# zumo_cam_01.net
KiCad netlist of a schematic drawn in EAGLE
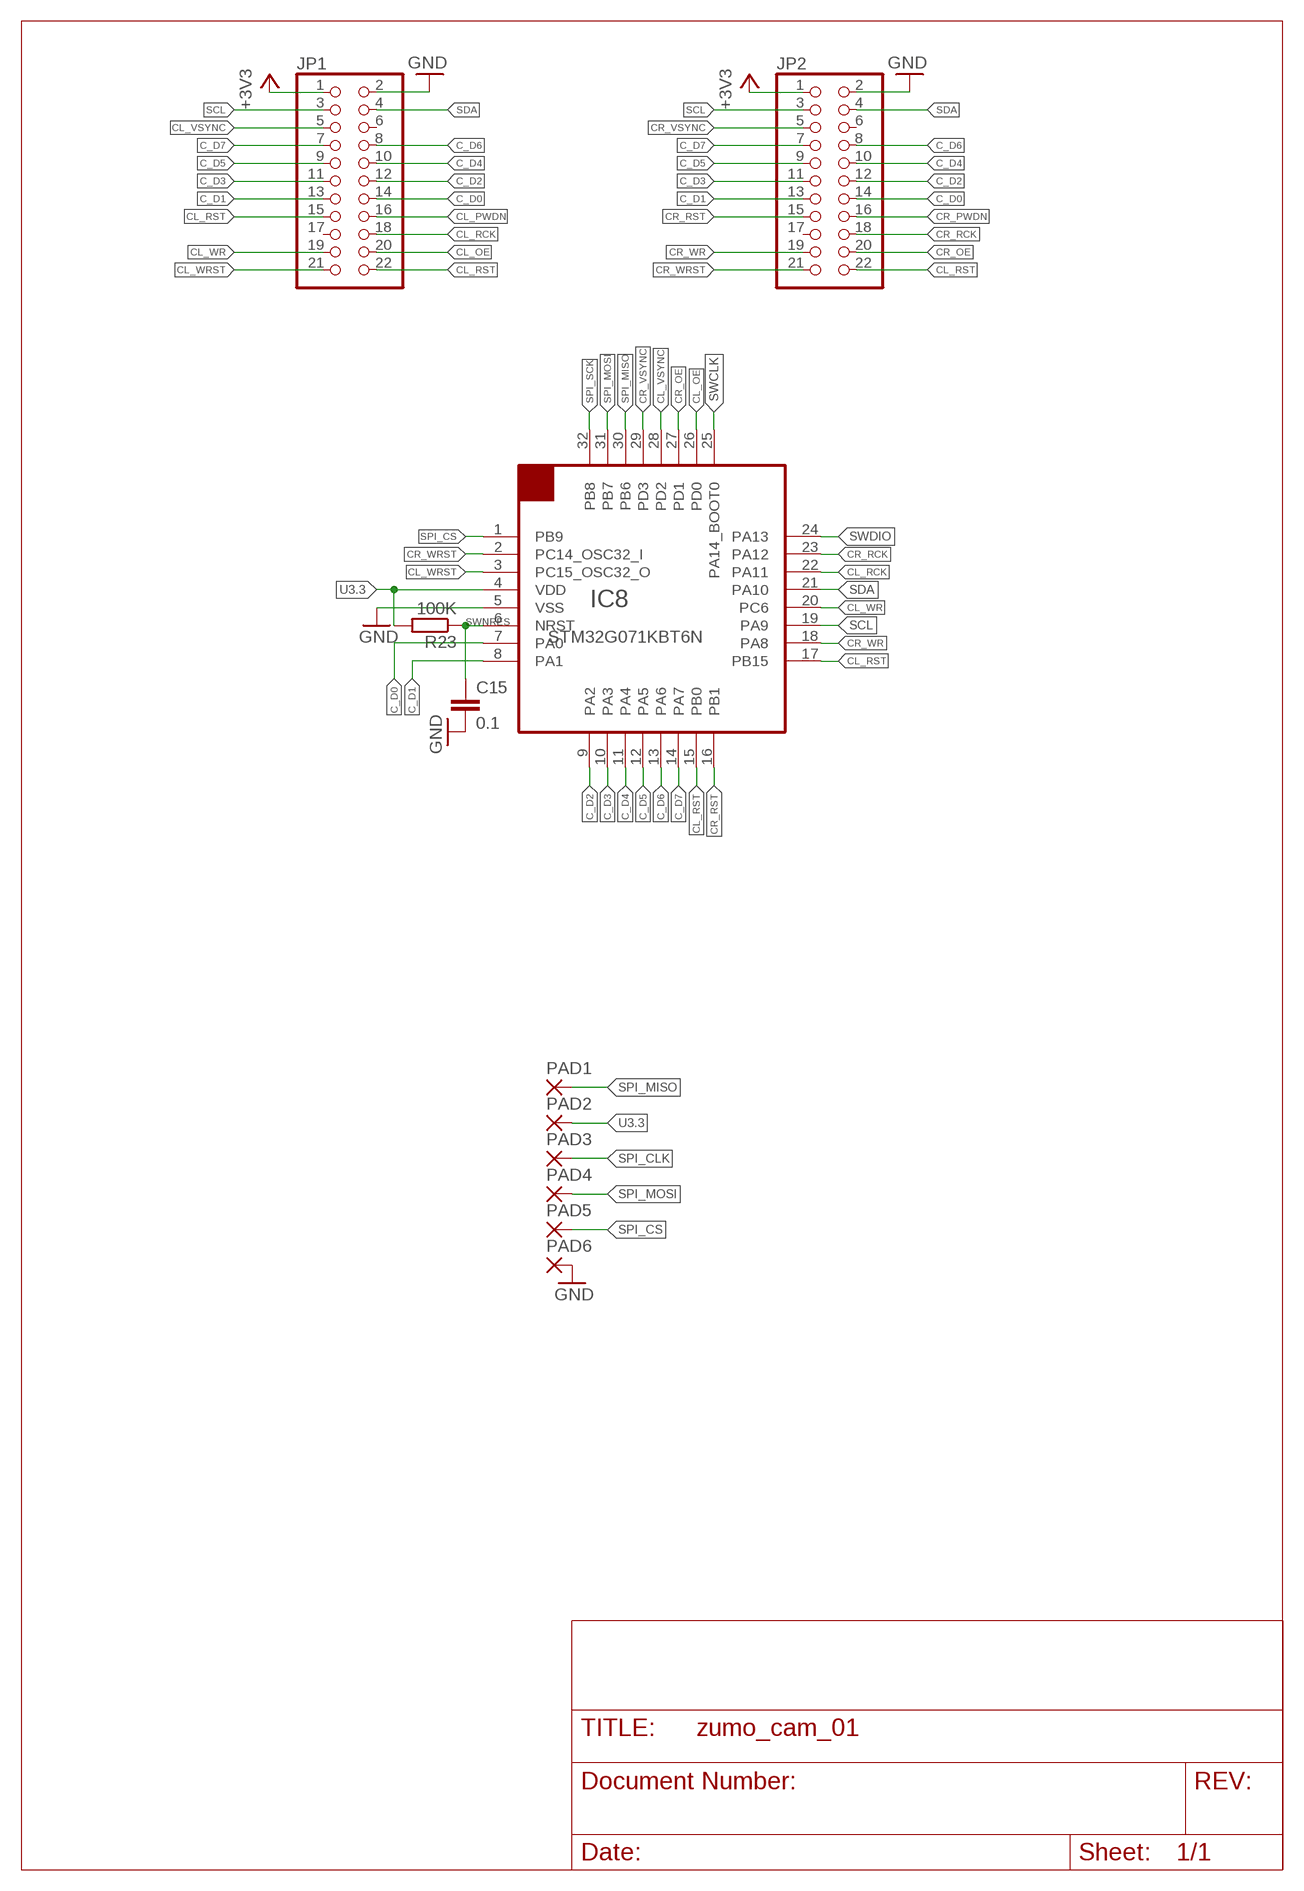
[diagram p0: schematic, sheet 1]

(export (version "E")
  (design (tool "Eeschema 10.0.6"))
  (components
    (comp (ref "C15")
      (value "0.1")
      (footprint "eagle-import:C0805")
      (libsource (lib "eagle-import") (part "C-EUC0805"))
    )
    (comp (ref "IC8")
      (value "STM32G071KBT6N")
      (footprint "eagle-import:LQFP-32")
      (libsource (lib "eagle-import") (part "STM32G071KBT6N"))
    )
    (comp (ref "JP1")
      (value "PINHD-2X11_2.54-SMD")
      (footprint "eagle-import:2X11SMD")
      (libsource (lib "eagle-import") (part "PINHD-2X11_2.54-SMD"))
    )
    (comp (ref "JP2")
      (value "PINHD-2X11_2.54-SMD")
      (footprint "eagle-import:2X11SMD")
      (libsource (lib "eagle-import") (part "PINHD-2X11_2.54-SMD"))
    )
    (comp (ref "PAD1")
      (value "SMD2")
      (footprint "eagle-import:SMD1,27-2,54")
      (libsource (lib "eagle-import") (part "SMD2"))
    )
    (comp (ref "PAD2")
      (value "SMD2")
      (footprint "eagle-import:SMD1,27-2,54")
      (libsource (lib "eagle-import") (part "SMD2"))
    )
    (comp (ref "PAD3")
      (value "SMD2")
      (footprint "eagle-import:SMD1,27-2,54")
      (libsource (lib "eagle-import") (part "SMD2"))
    )
    (comp (ref "PAD4")
      (value "SMD2")
      (footprint "eagle-import:SMD1,27-2,54")
      (libsource (lib "eagle-import") (part "SMD2"))
    )
    (comp (ref "PAD5")
      (value "SMD2")
      (footprint "eagle-import:SMD1,27-2,54")
      (libsource (lib "eagle-import") (part "SMD2"))
    )
    (comp (ref "PAD6")
      (value "SMD2")
      (footprint "eagle-import:SMD1,27-2,54")
      (libsource (lib "eagle-import") (part "SMD2"))
    )
    (comp (ref "R23")
      (value "100K")
      (footprint "eagle-import:R0805")
      (libsource (lib "eagle-import") (part "R-EU_R0805"))
    )
  )
  (nets
    (net (code "1") (name "+3V3") (class "Default")
      (node (ref "JP1") (pin "1") (pinfunction "1_1") (pintype "passive"))
      (node (ref "JP2") (pin "1") (pinfunction "1_1") (pintype "passive"))
    )
    (net (code "2") (name "/SWNRES") (class "Default")
      (node (ref "C15") (pin "1") (pinfunction "1_1") (pintype "passive"))
      (node (ref "IC8") (pin "6") (pinfunction "NRST_6") (pintype "bidirectional"))
      (node (ref "R23") (pin "1") (pinfunction "1_1") (pintype "passive"))
    )
    (net (code "3") (name "CL_OE") (class "Default")
      (node (ref "IC8") (pin "26") (pinfunction "PD0_26") (pintype "bidirectional"))
      (node (ref "JP1") (pin "20") (pinfunction "20_20") (pintype "passive"))
    )
    (net (code "4") (name "CL_PWDN") (class "Default")
      (node (ref "JP1") (pin "16") (pinfunction "16_16") (pintype "passive"))
    )
    (net (code "5") (name "CL_RCK") (class "Default")
      (node (ref "IC8") (pin "22") (pinfunction "PA11_22") (pintype "bidirectional"))
      (node (ref "JP1") (pin "18") (pinfunction "18_18") (pintype "passive"))
    )
    (net (code "6") (name "CL_RST") (class "Default")
      (node (ref "IC8") (pin "15") (pinfunction "PB0_15") (pintype "bidirectional"))
      (node (ref "IC8") (pin "17") (pinfunction "PB15_17") (pintype "bidirectional"))
      (node (ref "JP1") (pin "15") (pinfunction "15_15") (pintype "passive"))
      (node (ref "JP1") (pin "22") (pinfunction "22_22") (pintype "passive"))
      (node (ref "JP2") (pin "22") (pinfunction "22_22") (pintype "passive"))
    )
    (net (code "7") (name "CL_VSYNC") (class "Default")
      (node (ref "IC8") (pin "28") (pinfunction "PD2_28") (pintype "bidirectional"))
      (node (ref "JP1") (pin "5") (pinfunction "5_5") (pintype "passive"))
    )
    (net (code "8") (name "CL_WR") (class "Default")
      (node (ref "IC8") (pin "20") (pinfunction "PC6_20") (pintype "bidirectional"))
      (node (ref "JP1") (pin "19") (pinfunction "19_19") (pintype "passive"))
    )
    (net (code "9") (name "CL_WRST") (class "Default")
      (node (ref "IC8") (pin "3") (pinfunction "PC15_OSC32_O_3") (pintype "bidirectional"))
      (node (ref "JP1") (pin "21") (pinfunction "21_21") (pintype "passive"))
    )
    (net (code "10") (name "CR_OE") (class "Default")
      (node (ref "IC8") (pin "27") (pinfunction "PD1_27") (pintype "bidirectional"))
      (node (ref "JP2") (pin "20") (pinfunction "20_20") (pintype "passive"))
    )
    (net (code "11") (name "CR_PWDN") (class "Default")
      (node (ref "JP2") (pin "16") (pinfunction "16_16") (pintype "passive"))
    )
    (net (code "12") (name "CR_RCK") (class "Default")
      (node (ref "IC8") (pin "23") (pinfunction "PA12_23") (pintype "bidirectional"))
      (node (ref "JP2") (pin "18") (pinfunction "18_18") (pintype "passive"))
    )
    (net (code "13") (name "CR_RST") (class "Default")
      (node (ref "IC8") (pin "16") (pinfunction "PB1_16") (pintype "bidirectional"))
      (node (ref "JP2") (pin "15") (pinfunction "15_15") (pintype "passive"))
    )
    (net (code "14") (name "CR_VSYNC") (class "Default")
      (node (ref "IC8") (pin "29") (pinfunction "PD3_29") (pintype "bidirectional"))
      (node (ref "JP2") (pin "5") (pinfunction "5_5") (pintype "passive"))
    )
    (net (code "15") (name "CR_WR") (class "Default")
      (node (ref "IC8") (pin "18") (pinfunction "PA8_18") (pintype "bidirectional"))
      (node (ref "JP2") (pin "19") (pinfunction "19_19") (pintype "passive"))
    )
    (net (code "16") (name "CR_WRST") (class "Default")
      (node (ref "IC8") (pin "2") (pinfunction "PC14_OSC32_I_2") (pintype "bidirectional"))
      (node (ref "JP2") (pin "21") (pinfunction "21_21") (pintype "passive"))
    )
    (net (code "17") (name "C_D0") (class "Default")
      (node (ref "IC8") (pin "7") (pinfunction "PA0_7") (pintype "bidirectional"))
      (node (ref "JP1") (pin "14") (pinfunction "14_14") (pintype "passive"))
      (node (ref "JP2") (pin "14") (pinfunction "14_14") (pintype "passive"))
    )
    (net (code "18") (name "C_D1") (class "Default")
      (node (ref "IC8") (pin "8") (pinfunction "PA1_8") (pintype "bidirectional"))
      (node (ref "JP1") (pin "13") (pinfunction "13_13") (pintype "passive"))
      (node (ref "JP2") (pin "13") (pinfunction "13_13") (pintype "passive"))
    )
    (net (code "19") (name "C_D2") (class "Default")
      (node (ref "IC8") (pin "9") (pinfunction "PA2_9") (pintype "bidirectional"))
      (node (ref "JP1") (pin "12") (pinfunction "12_12") (pintype "passive"))
      (node (ref "JP2") (pin "12") (pinfunction "12_12") (pintype "passive"))
    )
    (net (code "20") (name "C_D3") (class "Default")
      (node (ref "IC8") (pin "10") (pinfunction "PA3_10") (pintype "bidirectional"))
      (node (ref "JP1") (pin "11") (pinfunction "11_11") (pintype "passive"))
      (node (ref "JP2") (pin "11") (pinfunction "11_11") (pintype "passive"))
    )
    (net (code "21") (name "C_D4") (class "Default")
      (node (ref "IC8") (pin "11") (pinfunction "PA4_11") (pintype "bidirectional"))
      (node (ref "JP1") (pin "10") (pinfunction "10_10") (pintype "passive"))
      (node (ref "JP2") (pin "10") (pinfunction "10_10") (pintype "passive"))
    )
    (net (code "22") (name "C_D5") (class "Default")
      (node (ref "IC8") (pin "12") (pinfunction "PA5_12") (pintype "bidirectional"))
      (node (ref "JP1") (pin "9") (pinfunction "9_9") (pintype "passive"))
      (node (ref "JP2") (pin "9") (pinfunction "9_9") (pintype "passive"))
    )
    (net (code "23") (name "C_D6") (class "Default")
      (node (ref "IC8") (pin "13") (pinfunction "PA6_13") (pintype "bidirectional"))
      (node (ref "JP1") (pin "8") (pinfunction "8_8") (pintype "passive"))
      (node (ref "JP2") (pin "8") (pinfunction "8_8") (pintype "passive"))
    )
    (net (code "24") (name "C_D7") (class "Default")
      (node (ref "IC8") (pin "14") (pinfunction "PA7_14") (pintype "bidirectional"))
      (node (ref "JP1") (pin "7") (pinfunction "7_7") (pintype "passive"))
      (node (ref "JP2") (pin "7") (pinfunction "7_7") (pintype "passive"))
    )
    (net (code "25") (name "GND") (class "Default")
      (node (ref "C15") (pin "2") (pinfunction "2_2") (pintype "passive"))
      (node (ref "IC8") (pin "5") (pinfunction "VSS_5") (pintype "power_in"))
      (node (ref "JP1") (pin "2") (pinfunction "2_2") (pintype "passive"))
      (node (ref "JP2") (pin "2") (pinfunction "2_2") (pintype "passive"))
      (node (ref "PAD6") (pin "1") (pinfunction "P_1") (pintype "passive"))
    )
    (net (code "26") (name "SCL") (class "Default")
      (node (ref "IC8") (pin "19") (pinfunction "PA9_19") (pintype "bidirectional"))
      (node (ref "JP1") (pin "3") (pinfunction "3_3") (pintype "passive"))
      (node (ref "JP2") (pin "3") (pinfunction "3_3") (pintype "passive"))
    )
    (net (code "27") (name "SDA") (class "Default")
      (node (ref "IC8") (pin "21") (pinfunction "PA10_21") (pintype "bidirectional"))
      (node (ref "JP1") (pin "4") (pinfunction "4_4") (pintype "passive"))
      (node (ref "JP2") (pin "4") (pinfunction "4_4") (pintype "passive"))
    )
    (net (code "28") (name "SPI_CLK") (class "Default")
      (node (ref "PAD3") (pin "1") (pinfunction "P_1") (pintype "passive"))
    )
    (net (code "29") (name "SPI_CS") (class "Default")
      (node (ref "IC8") (pin "1") (pinfunction "PB9_1") (pintype "bidirectional"))
      (node (ref "PAD5") (pin "1") (pinfunction "P_1") (pintype "passive"))
    )
    (net (code "30") (name "SPI_MISO") (class "Default")
      (node (ref "IC8") (pin "30") (pinfunction "PB6_30") (pintype "bidirectional"))
      (node (ref "PAD1") (pin "1") (pinfunction "P_1") (pintype "passive"))
    )
    (net (code "31") (name "SPI_MOSI") (class "Default")
      (node (ref "IC8") (pin "31") (pinfunction "PB7_31") (pintype "bidirectional"))
      (node (ref "PAD4") (pin "1") (pinfunction "P_1") (pintype "passive"))
    )
    (net (code "32") (name "SPI_SCK") (class "Default")
      (node (ref "IC8") (pin "32") (pinfunction "PB8_32") (pintype "bidirectional"))
    )
    (net (code "33") (name "SWCLK") (class "Default")
      (node (ref "IC8") (pin "25") (pinfunction "PA14_BOOT0_25") (pintype "bidirectional"))
    )
    (net (code "34") (name "SWDIO") (class "Default")
      (node (ref "IC8") (pin "24") (pinfunction "PA13_24") (pintype "bidirectional"))
    )
    (net (code "35") (name "U3.3") (class "Default")
      (node (ref "IC8") (pin "4") (pinfunction "VDD_4") (pintype "power_in"))
      (node (ref "PAD2") (pin "1") (pinfunction "P_1") (pintype "passive"))
      (node (ref "R23") (pin "2") (pinfunction "2_2") (pintype "passive"))
    )
    (net (code "36") (name "unconnected-(JP1-Pad6)") (class "Default")
      (node (ref "JP1") (pin "6") (pinfunction "6_6") (pintype "passive"))
    )
    (net (code "37") (name "unconnected-(JP1-Pad17)") (class "Default")
      (node (ref "JP1") (pin "17") (pinfunction "17_17") (pintype "passive"))
    )
    (net (code "38") (name "unconnected-(JP2-Pad6)") (class "Default")
      (node (ref "JP2") (pin "6") (pinfunction "6_6") (pintype "passive"))
    )
    (net (code "39") (name "unconnected-(JP2-Pad17)") (class "Default")
      (node (ref "JP2") (pin "17") (pinfunction "17_17") (pintype "passive"))
    )
  )
)
